# CANBedV1_1.net
KiCad netlist of a schematic drawn in EAGLE
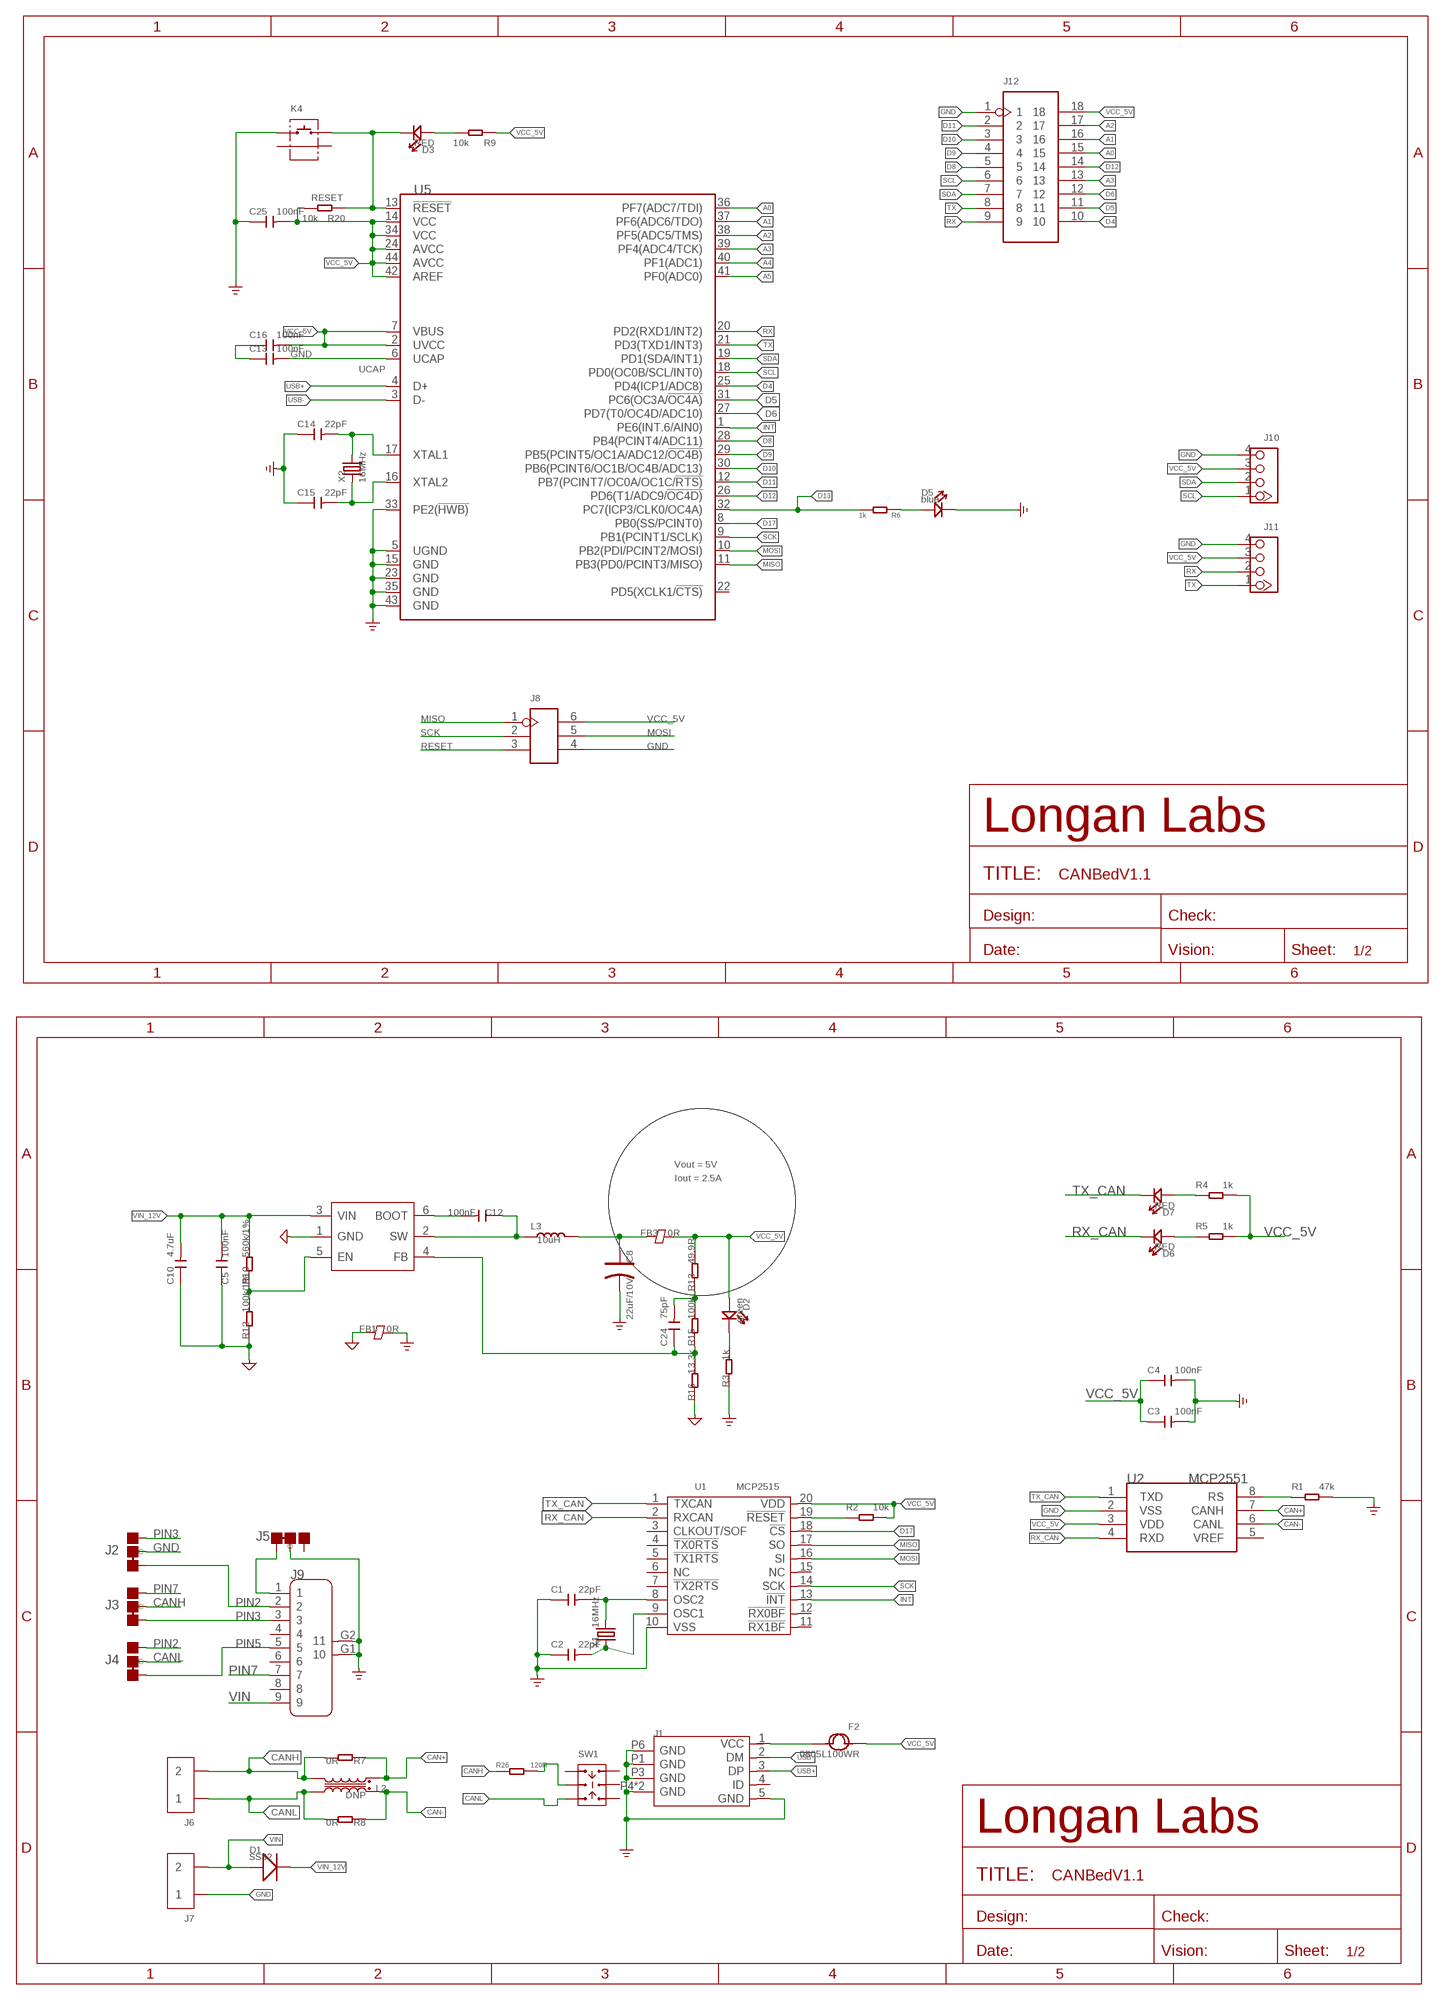
[diagram p0: schematic, sheet 1]

(export (version "E")
  (design (tool "Eeschema 10.0.6"))
  (components
    (comp (ref "C1")
      (value "22pF")
      (footprint "eagle-import:C0603")
      (libsource (lib "eagle-import") (part "CAP-0603"))
    )
    (comp (ref "C2")
      (value "22pF")
      (footprint "eagle-import:C0603")
      (libsource (lib "eagle-import") (part "CAP-0603"))
    )
    (comp (ref "C3")
      (value "100nF")
      (footprint "eagle-import:C0603")
      (libsource (lib "eagle-import") (part "CAP-0603"))
    )
    (comp (ref "C4")
      (value "100nF")
      (footprint "eagle-import:C0603")
      (libsource (lib "eagle-import") (part "CAP-0603"))
    )
    (comp (ref "C5")
      (value "100nF")
      (footprint "eagle-import:C0603")
      (libsource (lib "eagle-import") (part "CAP-0603"))
    )
    (comp (ref "C8")
      (value "22uF/10V")
      (footprint "eagle-import:AVX-B")
      (libsource (lib "eagle-import") (part "CAP-POLAR-AVX-B"))
    )
    (comp (ref "C10")
      (value "4.7uF")
      (footprint "eagle-import:C1206")
      (libsource (lib "eagle-import") (part "CAP-1206"))
    )
    (comp (ref "C12")
      (value "100nF")
      (footprint "eagle-import:C0603")
      (libsource (lib "eagle-import") (part "CAP-0603"))
    )
    (comp (ref "C13")
      (value "100nF")
      (footprint "eagle-import:C0603")
      (libsource (lib "eagle-import") (part "CAP-0603"))
    )
    (comp (ref "C14")
      (value "22pF")
      (footprint "eagle-import:C0603")
      (libsource (lib "eagle-import") (part "CAP-0603"))
    )
    (comp (ref "C15")
      (value "22pF")
      (footprint "eagle-import:C0603")
      (libsource (lib "eagle-import") (part "CAP-0603"))
    )
    (comp (ref "C16")
      (value "100nF")
      (footprint "eagle-import:C0603")
      (libsource (lib "eagle-import") (part "CAP-0603"))
    )
    (comp (ref "C24")
      (value "75pF")
      (footprint "eagle-import:C0603")
      (libsource (lib "eagle-import") (part "CAP-0603"))
    )
    (comp (ref "C25")
      (value "100nF")
      (footprint "eagle-import:C0603")
      (libsource (lib "eagle-import") (part "CAP-0603"))
    )
    (comp (ref "D1")
      (value "SS32")
      (footprint "eagle-import:DO-214AC")
      (libsource (lib "eagle-import") (part "DIODE'SMA'"))
    )
    (comp (ref "D2")
      (value "green")
      (footprint "eagle-import:LED-0603")
      (libsource (lib "eagle-import") (part "LED'0603'"))
    )
    (comp (ref "D3")
      (value "RED")
      (footprint "eagle-import:LED-0603")
      (libsource (lib "eagle-import") (part "LED'0603'"))
    )
    (comp (ref "D5")
      (value "blue")
      (footprint "eagle-import:LED-0603")
      (libsource (lib "eagle-import") (part "LED'0603'"))
    )
    (comp (ref "D6")
      (value "RED")
      (footprint "eagle-import:LED-0603")
      (libsource (lib "eagle-import") (part "LED'0603'"))
    )
    (comp (ref "D7")
      (value "RED")
      (footprint "eagle-import:LED-0603")
      (libsource (lib "eagle-import") (part "LED'0603'"))
    )
    (comp (ref "F2")
      (value "0805L100WR")
      (footprint "eagle-import:F0805")
      (libsource (lib "eagle-import") (part "FUSE0805"))
    )
    (comp (ref "FB1")
      (value "0R")
      (footprint "eagle-import:F0805")
      (libsource (lib "eagle-import") (part "FERRITE-BEAD-0805"))
    )
    (comp (ref "FB3")
      (value "0R")
      (footprint "eagle-import:F0805")
      (libsource (lib "eagle-import") (part "FERRITE-BEAD-0805"))
    )
    (comp (ref "J1")
      (value "MICRO-USB5+4P-320010050")
      (footprint "eagle-import:MICRO-USB5+5P-SMD-0.65-7.2X5.06MM")
      (libsource (lib "eagle-import") (part "MICRO-USB5+4P-320010050"))
    )
    (comp (ref "J2")
      (value "JUMPER-3P-SHORT")
      (footprint "eagle-import:3P-SMD-SHORT")
      (libsource (lib "eagle-import") (part "JUMPER-3P-SHORT"))
    )
    (comp (ref "J3")
      (value "JUMPER-3P-SHORT")
      (footprint "eagle-import:3P-SMD-SHORT")
      (libsource (lib "eagle-import") (part "JUMPER-3P-SHORT"))
    )
    (comp (ref "J4")
      (value "JUMPER-3P-SHORT")
      (footprint "eagle-import:3P-SMD-SHORT")
      (libsource (lib "eagle-import") (part "JUMPER-3P-SHORT"))
    )
    (comp (ref "J5")
      (value "JUMPER-3P-SHORT")
      (footprint "eagle-import:3P-SMD-SHORT")
      (libsource (lib "eagle-import") (part "JUMPER-3P-SHORT"))
    )
    (comp (ref "J6")
      (value "SCREW-TERMINAL-2P'5.08'")
      (footprint "eagle-import:H2-5.0-10.5X8.0MM")
      (libsource (lib "eagle-import") (part "SCREW-TERMINAL-2P'5.08'"))
    )
    (comp (ref "J7")
      (value "SCREW-TERMINAL-2P'5.08'")
      (footprint "eagle-import:H2-5.0-10.5X8.0MM")
      (libsource (lib "eagle-import") (part "SCREW-TERMINAL-2P'5.08'"))
    )
    (comp (ref "J8")
      (value "HEADER-2X3P-2.54")
      (footprint "eagle-import:H2X3-2.54")
      (libsource (lib "eagle-import") (part "HEADER-2X3P-2.54"))
    )
    (comp (ref "J9")
      (value "DB9'MEAL'")
      (footprint "eagle-import:DB9-MEAL")
      (libsource (lib "eagle-import") (part "DB9'MEAL'"))
    )
    (comp (ref "J10")
      (value "320110033")
      (footprint "eagle-import:HW4-2.0")
      (libsource (lib "eagle-import") (part "GROVE-CONNECTOR-DIP-2.0"))
    )
    (comp (ref "J11")
      (value "320110033")
      (footprint "eagle-import:HW4-2.0")
      (libsource (lib "eagle-import") (part "GROVE-CONNECTOR-DIP-2.0"))
    )
    (comp (ref "J12")
      (value "HEADER-2X9P-2.54")
      (footprint "eagle-import:H2X9-2.54")
      (libsource (lib "eagle-import") (part "HEADER-2X9P-2.54"))
    )
    (comp (ref "K4")
      (value "BUTTON-2+2P")
      (footprint "eagle-import:SW2+2P-7.7X2.75X3.95MM")
      (libsource (lib "eagle-import") (part "BUTTON-2+2P"))
    )
    (comp (ref "L2")
      (value "DNP")
      (footprint "eagle-import:INT4-0.85-2X1.25X1.2MM")
      (libsource (lib "eagle-import") (part "INDUCTOR-COMMON-MODE-SRF2012-900YA"))
    )
    (comp (ref "L3")
      (value "10uH")
      (footprint "eagle-import:INT2-SMD-6.6X7.1X3MM")
      (libsource (lib "eagle-import") (part "INDUCTOR-6.6X7.1"))
    )
    (comp (ref "R1")
      (value "47k")
      (footprint "eagle-import:R0603")
      (libsource (lib "eagle-import") (part "RES-0603"))
    )
    (comp (ref "R2")
      (value "10k")
      (footprint "eagle-import:R0603")
      (libsource (lib "eagle-import") (part "RES-0603"))
    )
    (comp (ref "R3")
      (value "1k")
      (footprint "eagle-import:R0603")
      (libsource (lib "eagle-import") (part "RES-0603"))
    )
    (comp (ref "R4")
      (value "1k")
      (footprint "eagle-import:R0603")
      (libsource (lib "eagle-import") (part "RES-0603"))
    )
    (comp (ref "R5")
      (value "1k")
      (footprint "eagle-import:R0603")
      (libsource (lib "eagle-import") (part "RES-0603"))
    )
    (comp (ref "R6")
      (value "1k")
      (footprint "eagle-import:R0603")
      (libsource (lib "eagle-import") (part "RES-0603"))
    )
    (comp (ref "R7")
      (value "0R")
      (footprint "eagle-import:R0603")
      (libsource (lib "eagle-import") (part "RES-0603"))
    )
    (comp (ref "R8")
      (value "0R")
      (footprint "eagle-import:R0603")
      (libsource (lib "eagle-import") (part "RES-0603"))
    )
    (comp (ref "R9")
      (value "10k")
      (footprint "eagle-import:R0603")
      (libsource (lib "eagle-import") (part "RES-0603"))
    )
    (comp (ref "R10")
      (value "560k/1%")
      (footprint "eagle-import:R0603")
      (libsource (lib "eagle-import") (part "RES-0603"))
    )
    (comp (ref "R12")
      (value "100k/1%")
      (footprint "eagle-import:R0603")
      (libsource (lib "eagle-import") (part "RES-0603"))
    )
    (comp (ref "R13")
      (value "49.9R")
      (footprint "eagle-import:R0603")
      (libsource (lib "eagle-import") (part "RES-0603"))
    )
    (comp (ref "R15")
      (value "100k")
      (footprint "eagle-import:R0603")
      (libsource (lib "eagle-import") (part "RES-0603"))
    )
    (comp (ref "R16")
      (value "13.3k")
      (footprint "eagle-import:R0603")
      (libsource (lib "eagle-import") (part "RES-0603"))
    )
    (comp (ref "R20")
      (value "10k")
      (footprint "eagle-import:R0603")
      (libsource (lib "eagle-import") (part "RES-0603"))
    )
    (comp (ref "R26")
      (value "120R")
      (footprint "eagle-import:R0603")
      (libsource (lib "eagle-import") (part "RES-0603"))
    )
    (comp (ref "SW1")
      (value "SWITCH-2CH-6P-311010004")
      (footprint "eagle-import:SW6-2.54-9.0X3.5X3.2+2.0MM")
      (libsource (lib "eagle-import") (part "SWITCH-2CH-6P-311010004"))
    )
    (comp (ref "U1")
      (value "MCP2515")
      (footprint "eagle-import:TSSOP20-0.65-6.5X4.4MM")
      (libsource (lib "eagle-import") (part "MCP2515'ST'"))
    )
    (comp (ref "U2")
      (value "MCP2551")
      (footprint "eagle-import:SOIC8-6.0")
      (libsource (lib "eagle-import") (part "MCP2551-SOIC8"))
    )
    (comp (ref "U5")
      (value "MCU-ATMEGA32U4-AU")
      (footprint "eagle-import:TQFP44-0.8-9.6X9.6MM")
      (libsource (lib "eagle-import") (part "MCU-ATMEGA32U4-AU"))
    )
    (comp (ref "U6")
      (value "PMIC-TPS54302")
      (footprint "eagle-import:SOT-23-6")
      (libsource (lib "eagle-import") (part "PMIC-TPS54302"))
    )
    (comp (ref "X1")
      (value "16MHz")
      (footprint "eagle-import:HC49US")
      (libsource (lib "eagle-import") (part "CRYSTAL-2P'HC49US'"))
    )
    (comp (ref "X2")
      (value "16MHz")
      (footprint "eagle-import:HC49US")
      (libsource (lib "eagle-import") (part "CRYSTAL-2P'HC49US'"))
    )
  )
  (nets
    (net (code "1") (name "A0") (class "Default")
      (node (ref "J12") (pin "15") (pinfunction "15_15") (pintype "bidirectional"))
      (node (ref "U5") (pin "36") (pinfunction "PF7(ADC7/TDI)_36") (pintype "bidirectional"))
    )
    (net (code "2") (name "A1") (class "Default")
      (node (ref "J12") (pin "16") (pinfunction "16_16") (pintype "bidirectional"))
      (node (ref "U5") (pin "37") (pinfunction "PF6(ADC6/TDO)_37") (pintype "bidirectional"))
    )
    (net (code "3") (name "A2") (class "Default")
      (node (ref "J12") (pin "17") (pinfunction "17_17") (pintype "bidirectional"))
      (node (ref "U5") (pin "38") (pinfunction "PF5(ADC5/TMS)_38") (pintype "bidirectional"))
    )
    (net (code "4") (name "A3") (class "Default")
      (node (ref "J12") (pin "13") (pinfunction "13_13") (pintype "bidirectional"))
      (node (ref "U5") (pin "39") (pinfunction "PF4(ADC4/TCK)_39") (pintype "bidirectional"))
    )
    (net (code "5") (name "A4") (class "Default")
      (node (ref "U5") (pin "40") (pinfunction "PF1(ADC1)_40") (pintype "bidirectional"))
    )
    (net (code "6") (name "A5") (class "Default")
      (node (ref "U5") (pin "41") (pinfunction "PF0(ADC0)_41") (pintype "bidirectional"))
    )
    (net (code "7") (name "AGND") (class "Default")
      (node (ref "C10") (pin "1") (pinfunction "1_1") (pintype "passive"))
      (node (ref "C5") (pin "1") (pinfunction "1_1") (pintype "passive"))
      (node (ref "FB1") (pin "1") (pinfunction "1_1") (pintype "bidirectional"))
      (node (ref "R12") (pin "1") (pinfunction "1_1") (pintype "passive"))
      (node (ref "R16") (pin "1") (pinfunction "1_1") (pintype "passive"))
      (node (ref "U6") (pin "1") (pinfunction "GND_1") (pintype "bidirectional"))
    )
    (net (code "8") (name "CAN+") (class "Default")
      (node (ref "L2") (pin "4") (pinfunction "4_4") (pintype "bidirectional"))
      (node (ref "R7") (pin "1") (pinfunction "1_1") (pintype "passive"))
      (node (ref "U2") (pin "7") (pinfunction "CANH_7") (pintype "bidirectional"))
    )
    (net (code "9") (name "CAN-") (class "Default")
      (node (ref "L2") (pin "1") (pinfunction "1_1") (pintype "bidirectional"))
      (node (ref "R8") (pin "1") (pinfunction "1_1") (pintype "passive"))
      (node (ref "U2") (pin "6") (pinfunction "CANL_6") (pintype "bidirectional"))
    )
    (net (code "10") (name "CANH") (class "Default")
      (node (ref "J3") (pin "MM") (pinfunction "C_MM") (pintype "bidirectional"))
      (node (ref "J6") (pin "2") (pinfunction "2_2") (pintype "bidirectional"))
      (node (ref "L2") (pin "3") (pinfunction "3_3") (pintype "bidirectional"))
      (node (ref "R26") (pin "1") (pinfunction "1_1") (pintype "passive"))
      (node (ref "R7") (pin "2") (pinfunction "2_2") (pintype "passive"))
    )
    (net (code "11") (name "CANL") (class "Default")
      (node (ref "J4") (pin "MM") (pinfunction "C_MM") (pintype "bidirectional"))
      (node (ref "J6") (pin "1") (pinfunction "1_1") (pintype "bidirectional"))
      (node (ref "L2") (pin "2") (pinfunction "2_2") (pintype "bidirectional"))
      (node (ref "R8") (pin "2") (pinfunction "2_2") (pintype "passive"))
      (node (ref "SW1") (pin "CH1B") (pinfunction "CH1B_CH1B") (pintype "bidirectional"))
    )
    (net (code "12") (name "D4") (class "Default")
      (node (ref "J12") (pin "10") (pinfunction "10_10") (pintype "bidirectional"))
      (node (ref "U5") (pin "25") (pinfunction "PD4(ICP1/ADC8)_25") (pintype "bidirectional"))
    )
    (net (code "13") (name "D5") (class "Default")
      (node (ref "J12") (pin "11") (pinfunction "11_11") (pintype "bidirectional"))
      (node (ref "U5") (pin "31") (pinfunction "PC6(OC3A/~{OC4A})_31") (pintype "bidirectional"))
    )
    (net (code "14") (name "D6") (class "Default")
      (node (ref "J12") (pin "12") (pinfunction "12_12") (pintype "bidirectional"))
      (node (ref "U5") (pin "27") (pinfunction "PD7(T0/OC4D/ADC10)_27") (pintype "bidirectional"))
    )
    (net (code "15") (name "D8") (class "Default")
      (node (ref "J12") (pin "5") (pinfunction "5_5") (pintype "bidirectional"))
      (node (ref "U5") (pin "28") (pinfunction "PB4(PCINT4/ADC11)_28") (pintype "bidirectional"))
    )
    (net (code "16") (name "D9") (class "Default")
      (node (ref "J12") (pin "4") (pinfunction "4_4") (pintype "bidirectional"))
      (node (ref "U5") (pin "29") (pinfunction "PB5(PCINT5/OC1A/ADC12/~{OC4B})_29") (pintype "bidirectional"))
    )
    (net (code "17") (name "D10") (class "Default")
      (node (ref "J12") (pin "3") (pinfunction "3_3") (pintype "bidirectional"))
      (node (ref "U5") (pin "30") (pinfunction "PB6(PCINT6/OC1B/OC4B/ADC13)_30") (pintype "bidirectional"))
    )
    (net (code "18") (name "D11") (class "Default")
      (node (ref "J12") (pin "2") (pinfunction "2_2") (pintype "bidirectional"))
      (node (ref "U5") (pin "12") (pinfunction "PB7(PCINT7/OC0A/OC1C/~{RTS})_12") (pintype "bidirectional"))
    )
    (net (code "19") (name "D12") (class "Default")
      (node (ref "J12") (pin "14") (pinfunction "14_14") (pintype "bidirectional"))
      (node (ref "U5") (pin "26") (pinfunction "PD6(T1/ADC9/~{OC4D})_26") (pintype "bidirectional"))
    )
    (net (code "20") (name "D13") (class "Default")
      (node (ref "R6") (pin "2") (pinfunction "2_2") (pintype "passive"))
      (node (ref "U5") (pin "32") (pinfunction "PC7(ICP3/CLK0/OC4A)_32") (pintype "bidirectional"))
    )
    (net (code "21") (name "D17") (class "Default")
      (node (ref "U1") (pin "18") (pinfunction "~{CS}_18") (pintype "bidirectional"))
      (node (ref "U5") (pin "8") (pinfunction "PB0(SS/PCINT0)_8") (pintype "bidirectional"))
    )
    (net (code "22") (name "GND") (class "Default")
      (node (ref "C1") (pin "1") (pinfunction "1_1") (pintype "passive"))
      (node (ref "C13") (pin "1") (pinfunction "1_1") (pintype "passive"))
      (node (ref "C14") (pin "1") (pinfunction "1_1") (pintype "passive"))
      (node (ref "C15") (pin "1") (pinfunction "1_1") (pintype "passive"))
      (node (ref "C16") (pin "1") (pinfunction "1_1") (pintype "passive"))
      (node (ref "C2") (pin "1") (pinfunction "1_1") (pintype "passive"))
      (node (ref "C25") (pin "1") (pinfunction "1_1") (pintype "passive"))
      (node (ref "C3") (pin "2") (pinfunction "2_2") (pintype "passive"))
      (node (ref "C4") (pin "2") (pinfunction "2_2") (pintype "passive"))
      (node (ref "C8") (pin "-") (pinfunction "-_-") (pintype "passive"))
      (node (ref "D5") (pin "-") (pinfunction "-_-") (pintype "passive"))
      (node (ref "FB1") (pin "2") (pinfunction "2_2") (pintype "bidirectional"))
      (node (ref "J1") (pin "5") (pinfunction "GND_5") (pintype "bidirectional"))
      (node (ref "J1") (pin "P1") (pinfunction "GND_P1") (pintype "bidirectional"))
      (node (ref "J1") (pin "P3") (pinfunction "GND_P3") (pintype "bidirectional"))
      (node (ref "J1") (pin "P4") (pinfunction "GND_P4") (pintype "bidirectional"))
      (node (ref "J1") (pin "P5") (pinfunction "GND_P5") (pintype "bidirectional"))
      (node (ref "J1") (pin "P6") (pinfunction "GND_P6") (pintype "bidirectional"))
      (node (ref "J10") (pin "4") (pinfunction "4_4") (pintype "bidirectional"))
      (node (ref "J11") (pin "4") (pinfunction "4_4") (pintype "bidirectional"))
      (node (ref "J12") (pin "1") (pinfunction "1_1") (pintype "bidirectional"))
      (node (ref "J2") (pin "MM") (pinfunction "C_MM") (pintype "bidirectional"))
      (node (ref "J5") (pin "MM") (pinfunction "C_MM") (pintype "bidirectional"))
      (node (ref "J7") (pin "1") (pinfunction "1_1") (pintype "bidirectional"))
      (node (ref "J8") (pin "4") (pinfunction "4_4") (pintype "bidirectional"))
      (node (ref "J9") (pin "G1") (pinfunction "10_G1") (pintype "bidirectional"))
      (node (ref "J9") (pin "G2") (pinfunction "11_G2") (pintype "bidirectional"))
      (node (ref "K4") (pin "1") (pinfunction "1_1") (pintype "bidirectional"))
      (node (ref "R1") (pin "2") (pinfunction "2_2") (pintype "passive"))
      (node (ref "R3") (pin "1") (pinfunction "1_1") (pintype "passive"))
      (node (ref "U1") (pin "10") (pinfunction "VSS_10") (pintype "bidirectional"))
      (node (ref "U2") (pin "2") (pinfunction "VSS_2") (pintype "bidirectional"))
      (node (ref "U5") (pin "15") (pinfunction "GND_15") (pintype "bidirectional"))
      (node (ref "U5") (pin "23") (pinfunction "GND_23") (pintype "bidirectional"))
      (node (ref "U5") (pin "33") (pinfunction "PE2(~{HWB})_33") (pintype "bidirectional"))
      (node (ref "U5") (pin "35") (pinfunction "GND_35") (pintype "bidirectional"))
      (node (ref "U5") (pin "43") (pinfunction "GND_43") (pintype "bidirectional"))
      (node (ref "U5") (pin "5") (pinfunction "UGND_5") (pintype "bidirectional"))
    )
    (net (code "23") (name "INT") (class "Default")
      (node (ref "U1") (pin "13") (pinfunction "~{INT}_13") (pintype "bidirectional"))
      (node (ref "U5") (pin "1") (pinfunction "PE6(INT.6/AIN0)_1") (pintype "bidirectional"))
    )
    (net (code "24") (name "MISO") (class "Default")
      (node (ref "J8") (pin "1") (pinfunction "1_1") (pintype "bidirectional"))
      (node (ref "U1") (pin "17") (pinfunction "SO_17") (pintype "bidirectional"))
      (node (ref "U5") (pin "11") (pinfunction "PB3(PD0/PCINT3/MISO)_11") (pintype "bidirectional"))
    )
    (net (code "25") (name "MOSI") (class "Default")
      (node (ref "J8") (pin "5") (pinfunction "5_5") (pintype "bidirectional"))
      (node (ref "U1") (pin "16") (pinfunction "SI_16") (pintype "bidirectional"))
      (node (ref "U5") (pin "10") (pinfunction "PB2(PDI/PCINT2/MOSI)_10") (pintype "bidirectional"))
    )
    (net (code "26") (name "Net-(C8-Pad+)") (class "Default")
      (node (ref "C8") (pin "+") (pinfunction "+_+") (pintype "passive"))
      (node (ref "FB3") (pin "1") (pinfunction "1_1") (pintype "bidirectional"))
      (node (ref "L3") (pin "2") (pinfunction "2_2") (pintype "passive"))
    )
    (net (code "27") (name "Net-(C24-Pad2)") (class "Default")
      (node (ref "C24") (pin "2") (pinfunction "2_2") (pintype "passive"))
      (node (ref "R13") (pin "1") (pinfunction "1_1") (pintype "passive"))
      (node (ref "R15") (pin "2") (pinfunction "2_2") (pintype "passive"))
    )
    (net (code "28") (name "Net-(D2-Pad-)") (class "Default")
      (node (ref "D2") (pin "-") (pinfunction "-_-") (pintype "passive"))
      (node (ref "R3") (pin "2") (pinfunction "2_2") (pintype "passive"))
    )
    (net (code "29") (name "Net-(D3-Pad+)") (class "Default")
      (node (ref "D3") (pin "+") (pinfunction "+_+") (pintype "passive"))
      (node (ref "R9") (pin "2") (pinfunction "2_2") (pintype "passive"))
    )
    (net (code "30") (name "Net-(D5-Pad+)") (class "Default")
      (node (ref "D5") (pin "+") (pinfunction "+_+") (pintype "passive"))
      (node (ref "R6") (pin "1") (pinfunction "1_1") (pintype "passive"))
    )
    (net (code "31") (name "Net-(D6-Pad+)") (class "Default")
      (node (ref "D6") (pin "+") (pinfunction "+_+") (pintype "passive"))
      (node (ref "R5") (pin "1") (pinfunction "1_1") (pintype "passive"))
    )
    (net (code "32") (name "Net-(D7-Pad+)") (class "Default")
      (node (ref "D7") (pin "+") (pinfunction "+_+") (pintype "passive"))
      (node (ref "R4") (pin "1") (pinfunction "1_1") (pintype "passive"))
    )
    (net (code "33") (name "Net-(J1-VCC)") (class "Default")
      (node (ref "F2") (pin "2") (pinfunction "2_2") (pintype "bidirectional"))
      (node (ref "J1") (pin "1") (pinfunction "VCC_1") (pintype "bidirectional"))
    )
    (net (code "34") (name "Net-(J5-L)") (class "Default")
      (node (ref "J5") (pin "11") (pinfunction "L_11") (pintype "bidirectional"))
      (node (ref "J9") (pin "1") (pinfunction "1_1") (pintype "bidirectional"))
    )
    (net (code "35") (name "Net-(R26-Pad2)") (class "Default")
      (node (ref "R26") (pin "2") (pinfunction "2_2") (pintype "passive"))
      (node (ref "SW1") (pin "COM1") (pinfunction "COM1_COM1") (pintype "bidirectional"))
    )
    (net (code "36") (name "Net-(U1-OSC1)") (class "Default")
      (node (ref "C2") (pin "2") (pinfunction "2_2") (pintype "passive"))
      (node (ref "U1") (pin "9") (pinfunction "OSC1_9") (pintype "bidirectional"))
      (node (ref "X1") (pin "1") (pinfunction "1_1") (pintype "passive"))
    )
    (net (code "37") (name "Net-(U1-OSC2)") (class "Default")
      (node (ref "C1") (pin "2") (pinfunction "2_2") (pintype "passive"))
      (node (ref "U1") (pin "8") (pinfunction "OSC2_8") (pintype "bidirectional"))
      (node (ref "X1") (pin "2") (pinfunction "2_2") (pintype "passive"))
    )
    (net (code "38") (name "Net-(U1-~{RESET})") (class "Default")
      (node (ref "R2") (pin "1") (pinfunction "1_1") (pintype "passive"))
      (node (ref "U1") (pin "19") (pinfunction "~{RESET}_19") (pintype "bidirectional"))
    )
    (net (code "39") (name "Net-(U2-RS)") (class "Default")
      (node (ref "R1") (pin "1") (pinfunction "1_1") (pintype "passive"))
      (node (ref "U2") (pin "8") (pinfunction "RS_8") (pintype "bidirectional"))
    )
    (net (code "40") (name "Net-(U5-XTAL1)") (class "Default")
      (node (ref "C14") (pin "2") (pinfunction "2_2") (pintype "passive"))
      (node (ref "U5") (pin "17") (pinfunction "XTAL1_17") (pintype "bidirectional"))
      (node (ref "X2") (pin "2") (pinfunction "2_2") (pintype "passive"))
    )
    (net (code "41") (name "Net-(U5-XTAL2)") (class "Default")
      (node (ref "C15") (pin "2") (pinfunction "2_2") (pintype "passive"))
      (node (ref "U5") (pin "16") (pinfunction "XTAL2_16") (pintype "bidirectional"))
      (node (ref "X2") (pin "1") (pinfunction "1_1") (pintype "passive"))
    )
    (net (code "42") (name "Net-(U6-BOOT)") (class "Default")
      (node (ref "C12") (pin "2") (pinfunction "2_2") (pintype "passive"))
      (node (ref "U6") (pin "6") (pinfunction "BOOT_6") (pintype "bidirectional"))
    )
    (net (code "43") (name "Net-(U6-EN)") (class "Default")
      (node (ref "R10") (pin "1") (pinfunction "1_1") (pintype "passive"))
      (node (ref "R12") (pin "2") (pinfunction "2_2") (pintype "passive"))
      (node (ref "U6") (pin "5") (pinfunction "EN_5") (pintype "bidirectional"))
    )
    (net (code "44") (name "Net-(U6-FB)") (class "Default")
      (node (ref "C24") (pin "1") (pinfunction "1_1") (pintype "passive"))
      (node (ref "R15") (pin "1") (pinfunction "1_1") (pintype "passive"))
      (node (ref "R16") (pin "2") (pinfunction "2_2") (pintype "passive"))
      (node (ref "U6") (pin "4") (pinfunction "FB_4") (pintype "bidirectional"))
    )
    (net (code "45") (name "Net-(U6-SW)") (class "Default")
      (node (ref "C12") (pin "1") (pinfunction "1_1") (pintype "passive"))
      (node (ref "L3") (pin "1") (pinfunction "1_1") (pintype "passive"))
      (node (ref "U6") (pin "2") (pinfunction "SW_2") (pintype "bidirectional"))
    )
    (net (code "46") (name "PIN2") (class "Default")
      (node (ref "J2") (pin "11") (pinfunction "L_11") (pintype "bidirectional"))
      (node (ref "J4") (pin "00") (pinfunction "R_00") (pintype "bidirectional"))
      (node (ref "J9") (pin "2") (pinfunction "2_2") (pintype "bidirectional"))
    )
    (net (code "47") (name "PIN3") (class "Default")
      (node (ref "J2") (pin "00") (pinfunction "R_00") (pintype "bidirectional"))
      (node (ref "J3") (pin "11") (pinfunction "L_11") (pintype "bidirectional"))
      (node (ref "J9") (pin "3") (pinfunction "3_3") (pintype "bidirectional"))
    )
    (net (code "48") (name "PIN5") (class "Default")
      (node (ref "J4") (pin "11") (pinfunction "L_11") (pintype "bidirectional"))
      (node (ref "J9") (pin "5") (pinfunction "5_5") (pintype "bidirectional"))
    )
    (net (code "49") (name "PIN7") (class "Default")
      (node (ref "J3") (pin "00") (pinfunction "R_00") (pintype "bidirectional"))
      (node (ref "J9") (pin "7") (pinfunction "7_7") (pintype "bidirectional"))
    )
    (net (code "50") (name "RESET") (class "Default")
      (node (ref "D3") (pin "-") (pinfunction "-_-") (pintype "passive"))
      (node (ref "J8") (pin "3") (pinfunction "3_3") (pintype "bidirectional"))
      (node (ref "K4") (pin "2") (pinfunction "2_2") (pintype "bidirectional"))
      (node (ref "R20") (pin "1") (pinfunction "1_1") (pintype "passive"))
      (node (ref "U5") (pin "13") (pinfunction "~{RESET}_13") (pintype "bidirectional"))
    )
    (net (code "51") (name "RX") (class "Default")
      (node (ref "J11") (pin "2") (pinfunction "2_2") (pintype "bidirectional"))
      (node (ref "J12") (pin "9") (pinfunction "9_9") (pintype "bidirectional"))
      (node (ref "U5") (pin "20") (pinfunction "PD2(RXD1/INT2)_20") (pintype "bidirectional"))
    )
    (net (code "52") (name "RX_CAN") (class "Default")
      (node (ref "D6") (pin "-") (pinfunction "-_-") (pintype "passive"))
      (node (ref "U1") (pin "2") (pinfunction "RXCAN_2") (pintype "bidirectional"))
      (node (ref "U2") (pin "4") (pinfunction "RXD_4") (pintype "bidirectional"))
    )
    (net (code "53") (name "SCK") (class "Default")
      (node (ref "J8") (pin "2") (pinfunction "2_2") (pintype "bidirectional"))
      (node (ref "U1") (pin "14") (pinfunction "SCK_14") (pintype "bidirectional"))
      (node (ref "U5") (pin "9") (pinfunction "PB1(PCINT1/SCLK)_9") (pintype "bidirectional"))
    )
    (net (code "54") (name "SCL") (class "Default")
      (node (ref "J10") (pin "1") (pinfunction "1_1") (pintype "bidirectional"))
      (node (ref "J12") (pin "6") (pinfunction "6_6") (pintype "bidirectional"))
      (node (ref "U5") (pin "18") (pinfunction "PD0(OC0B/SCL/INT0)_18") (pintype "bidirectional"))
    )
    (net (code "55") (name "SDA") (class "Default")
      (node (ref "J10") (pin "2") (pinfunction "2_2") (pintype "bidirectional"))
      (node (ref "J12") (pin "7") (pinfunction "7_7") (pintype "bidirectional"))
      (node (ref "U5") (pin "19") (pinfunction "PD1(SDA/INT1)_19") (pintype "bidirectional"))
    )
    (net (code "56") (name "TX") (class "Default")
      (node (ref "J11") (pin "1") (pinfunction "1_1") (pintype "bidirectional"))
      (node (ref "J12") (pin "8") (pinfunction "8_8") (pintype "bidirectional"))
      (node (ref "U5") (pin "21") (pinfunction "PD3(TXD1/INT3)_21") (pintype "bidirectional"))
    )
    (net (code "57") (name "TX_CAN") (class "Default")
      (node (ref "D7") (pin "-") (pinfunction "-_-") (pintype "passive"))
      (node (ref "U1") (pin "1") (pinfunction "TXCAN_1") (pintype "bidirectional"))
      (node (ref "U2") (pin "1") (pinfunction "TXD_1") (pintype "bidirectional"))
    )
    (net (code "58") (name "UCAP") (class "Default")
      (node (ref "C13") (pin "2") (pinfunction "2_2") (pintype "passive"))
      (node (ref "U5") (pin "6") (pinfunction "UCAP_6") (pintype "bidirectional"))
    )
    (net (code "59") (name "USB+") (class "Default")
      (node (ref "J1") (pin "3") (pinfunction "DP_3") (pintype "bidirectional"))
      (node (ref "U5") (pin "4") (pinfunction "D+_4") (pintype "bidirectional"))
    )
    (net (code "60") (name "USB-") (class "Default")
      (node (ref "J1") (pin "2") (pinfunction "DM_2") (pintype "bidirectional"))
      (node (ref "U5") (pin "3") (pinfunction "D-_3") (pintype "bidirectional"))
    )
    (net (code "61") (name "VCC_5V") (class "Default")
      (node (ref "C16") (pin "2") (pinfunction "2_2") (pintype "passive"))
      (node (ref "C25") (pin "2") (pinfunction "2_2") (pintype "passive"))
      (node (ref "C3") (pin "1") (pinfunction "1_1") (pintype "passive"))
      (node (ref "C4") (pin "1") (pinfunction "1_1") (pintype "passive"))
      (node (ref "D2") (pin "+") (pinfunction "+_+") (pintype "passive"))
      (node (ref "F2") (pin "1") (pinfunction "1_1") (pintype "bidirectional"))
      (node (ref "FB3") (pin "2") (pinfunction "2_2") (pintype "bidirectional"))
      (node (ref "J10") (pin "3") (pinfunction "3_3") (pintype "bidirectional"))
      (node (ref "J11") (pin "3") (pinfunction "3_3") (pintype "bidirectional"))
      (node (ref "J12") (pin "18") (pinfunction "18_18") (pintype "bidirectional"))
      (node (ref "J8") (pin "6") (pinfunction "6_6") (pintype "bidirectional"))
      (node (ref "R13") (pin "2") (pinfunction "2_2") (pintype "passive"))
      (node (ref "R2") (pin "2") (pinfunction "2_2") (pintype "passive"))
      (node (ref "R20") (pin "2") (pinfunction "2_2") (pintype "passive"))
      (node (ref "R4") (pin "2") (pinfunction "2_2") (pintype "passive"))
      (node (ref "R5") (pin "2") (pinfunction "2_2") (pintype "passive"))
      (node (ref "R9") (pin "1") (pinfunction "1_1") (pintype "passive"))
      (node (ref "U1") (pin "20") (pinfunction "VDD_20") (pintype "bidirectional"))
      (node (ref "U2") (pin "3") (pinfunction "VDD_3") (pintype "bidirectional"))
      (node (ref "U5") (pin "14") (pinfunction "VCC_14") (pintype "bidirectional"))
      (node (ref "U5") (pin "2") (pinfunction "UVCC_2") (pintype "bidirectional"))
      (node (ref "U5") (pin "24") (pinfunction "AVCC_24") (pintype "bidirectional"))
      (node (ref "U5") (pin "34") (pinfunction "VCC_34") (pintype "bidirectional"))
      (node (ref "U5") (pin "42") (pinfunction "AREF_42") (pintype "bidirectional"))
      (node (ref "U5") (pin "44") (pinfunction "AVCC_44") (pintype "bidirectional"))
      (node (ref "U5") (pin "7") (pinfunction "VBUS_7") (pintype "bidirectional"))
    )
    (net (code "62") (name "VIN") (class "Default")
      (node (ref "D1") (pin "1") (pinfunction "+_1") (pintype "passive"))
      (node (ref "J7") (pin "2") (pinfunction "2_2") (pintype "bidirectional"))
      (node (ref "J9") (pin "9") (pinfunction "9_9") (pintype "bidirectional"))
    )
    (net (code "63") (name "VIN_12V") (class "Default")
      (node (ref "C10") (pin "2") (pinfunction "2_2") (pintype "passive"))
      (node (ref "C5") (pin "2") (pinfunction "2_2") (pintype "passive"))
      (node (ref "D1") (pin "2") (pinfunction "-_2") (pintype "passive"))
      (node (ref "R10") (pin "2") (pinfunction "2_2") (pintype "passive"))
      (node (ref "U6") (pin "3") (pinfunction "VIN_3") (pintype "bidirectional"))
    )
    (net (code "64") (name "unconnected-(J1-ID-Pad4)") (class "Default")
      (node (ref "J1") (pin "4") (pinfunction "ID_4") (pintype "bidirectional"))
    )
    (net (code "65") (name "unconnected-(J5-R-Pad00)") (class "Default")
      (node (ref "J5") (pin "00") (pinfunction "R_00") (pintype "bidirectional"))
    )
    (net (code "66") (name "unconnected-(J9-Pad4)") (class "Default")
      (node (ref "J9") (pin "4") (pinfunction "4_4") (pintype "bidirectional"))
    )
    (net (code "67") (name "unconnected-(J9-Pad6)") (class "Default")
      (node (ref "J9") (pin "6") (pinfunction "6_6") (pintype "bidirectional"))
    )
    (net (code "68") (name "unconnected-(J9-Pad8)") (class "Default")
      (node (ref "J9") (pin "8") (pinfunction "8_8") (pintype "bidirectional"))
    )
    (net (code "69") (name "unconnected-(K4-PadS1)") (class "Default")
      (node (ref "K4") (pin "S1") (pinfunction "S1_S1") (pintype "bidirectional"))
    )
    (net (code "70") (name "unconnected-(K4-PadS2)") (class "Default")
      (node (ref "K4") (pin "S2") (pinfunction "S2_S2") (pintype "bidirectional"))
    )
    (net (code "71") (name "unconnected-(SW1-PadCH1A)") (class "Default")
      (node (ref "SW1") (pin "CH1A") (pinfunction "CH1A_CH1A") (pintype "bidirectional"))
    )
    (net (code "72") (name "unconnected-(SW1-PadCH2A)") (class "Default")
      (node (ref "SW1") (pin "CH2A") (pinfunction "CH2A_CH2A") (pintype "bidirectional"))
    )
    (net (code "73") (name "unconnected-(SW1-PadCH2B)") (class "Default")
      (node (ref "SW1") (pin "CH2B") (pinfunction "CH2B_CH2B") (pintype "bidirectional"))
    )
    (net (code "74") (name "unconnected-(SW1-PadCOM2)") (class "Default")
      (node (ref "SW1") (pin "COM2") (pinfunction "COM2_COM2") (pintype "bidirectional"))
    )
    (net (code "75") (name "unconnected-(U1-CLKOUT{slash}SOF-Pad3)") (class "Default")
      (node (ref "U1") (pin "3") (pinfunction "CLKOUT/SOF_3") (pintype "bidirectional"))
    )
    (net (code "76") (name "unconnected-(U1-NC-Pad6)") (class "Default")
      (node (ref "U1") (pin "6") (pinfunction "NC_6") (pintype "bidirectional"))
    )
    (net (code "77") (name "unconnected-(U1-NC-Pad15)") (class "Default")
      (node (ref "U1") (pin "15") (pinfunction "NC_15") (pintype "bidirectional"))
    )
    (net (code "78") (name "unconnected-(U1-~{RX0BF}-Pad12)") (class "Default")
      (node (ref "U1") (pin "12") (pinfunction "~{RX0BF}_12") (pintype "bidirectional"))
    )
    (net (code "79") (name "unconnected-(U1-~{RX1BF}-Pad11)") (class "Default")
      (node (ref "U1") (pin "11") (pinfunction "~{RX1BF}_11") (pintype "bidirectional"))
    )
    (net (code "80") (name "unconnected-(U1-~{TX0RTS}-Pad4)") (class "Default")
      (node (ref "U1") (pin "4") (pinfunction "~{TX0RTS}_4") (pintype "bidirectional"))
    )
    (net (code "81") (name "unconnected-(U1-~{TX1RTS}-Pad5)") (class "Default")
      (node (ref "U1") (pin "5") (pinfunction "~{TX1RTS}_5") (pintype "bidirectional"))
    )
    (net (code "82") (name "unconnected-(U1-~{TX2RTS}-Pad7)") (class "Default")
      (node (ref "U1") (pin "7") (pinfunction "~{TX2RTS}_7") (pintype "bidirectional"))
    )
    (net (code "83") (name "unconnected-(U2-VREF-Pad5)") (class "Default")
      (node (ref "U2") (pin "5") (pinfunction "VREF_5") (pintype "bidirectional"))
    )
    (net (code "84") (name "unconnected-(U5-PD5(XCLK1{slash}~{CTS})-Pad22)") (class "Default")
      (node (ref "U5") (pin "22") (pinfunction "PD5(XCLK1/~{CTS})_22") (pintype "bidirectional"))
    )
  )
)
